# 5_spiFlash.net
KiCad netlist of a schematic drawn in Altium Designer
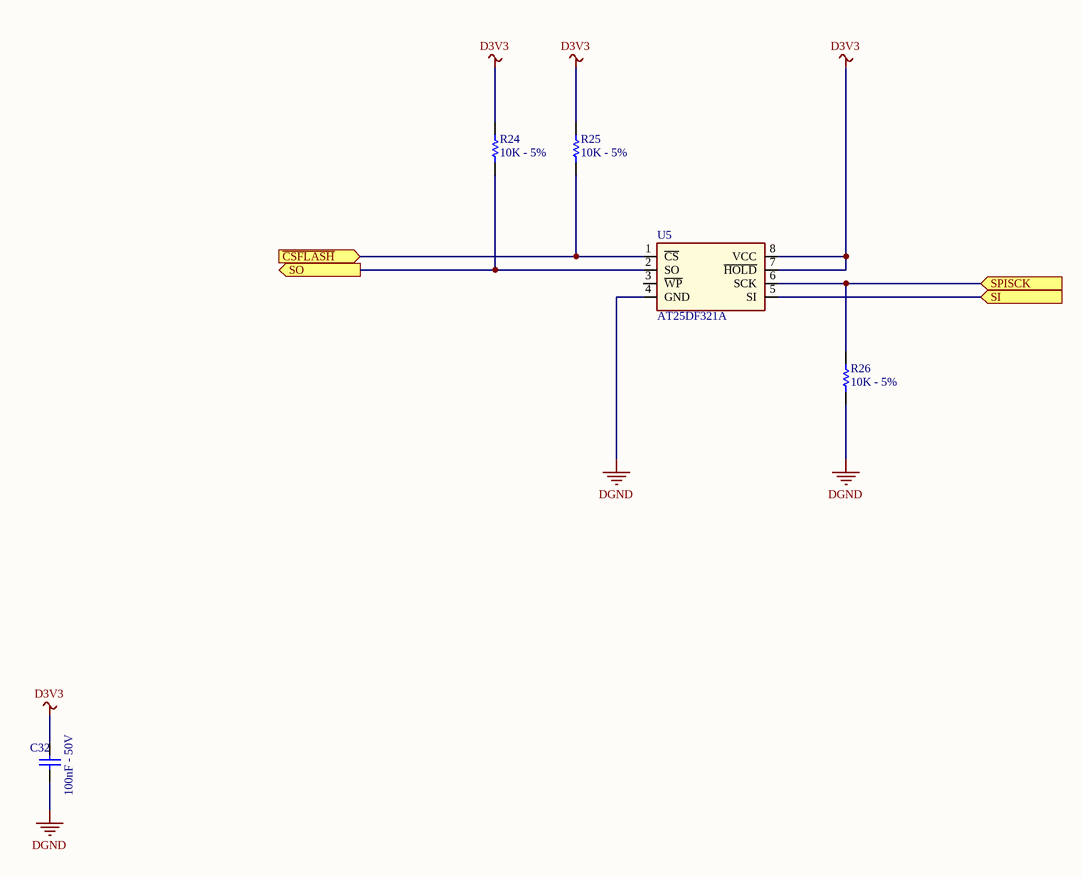
[diagram p0: 5_spiFlash.SchDoc]

(export (version "E")
  (design (tool "Eeschema 10.0.6"))
  (components
    (comp (ref "C32")
      (value "Capacitor 100 nF - 10%")
      (footprint "SMD0805-CAP")
      (description "Capacitor 100nF, 10%, SMD 0805")
      (fields
        (field (name "MANUFACTURER") "AVX")
        (field (name "PARTNUMBER") "08055C104KAT2A")
        (field (name "VALOR") "100nF - 50V")
      )
      (libsource (lib "Capacitor_smd") (part "100nF - 50V - 10% - 0805 - 580"))
    )
    (comp (ref "R24")
      (value "10K - 5% - 0805 - 328")
      (footprint "SMD0805")
      (description "Resistor 10K, 5%, SMD 0805")
      (fields
        (field (name "PARTNUMBER") "RC2012J103CS")
        (field (name "MANUFACTURER") "SAMSUNG")
        (field (name "VALOR") "10K - 5%")
      )
      (libsource (lib "Resistor_smd") (part "10K - 5% - 0805 - 328"))
    )
    (comp (ref "R25")
      (value "10K - 5% - 0805 - 328")
      (footprint "SMD0805")
      (description "Resistor 10K, 5%, SMD 0805")
      (fields
        (field (name "PARTNUMBER") "RC2012J103CS")
        (field (name "MANUFACTURER") "SAMSUNG")
        (field (name "VALOR") "10K - 5%")
      )
      (libsource (lib "Resistor_smd") (part "10K - 5% - 0805 - 328"))
    )
    (comp (ref "R26")
      (value "10K - 5% - 0805 - 328")
      (footprint "SMD0805")
      (description "Resistor 10K, 5%, SMD 0805")
      (fields
        (field (name "PARTNUMBER") "RC2012J103CS")
        (field (name "MANUFACTURER") "SAMSUNG")
        (field (name "VALOR") "10K - 5%")
      )
      (libsource (lib "Resistor_smd") (part "10K - 5% - 0805 - 328"))
    )
    (comp (ref "U5")
      (value "AT25DF321A (EIAJ SOIC) 5219")
      (footprint "BIQUAD.SOG.050/8/WG.325/L.200")
      (description "CI AT25DF321A")
      (fields
        (field (name "MANUFACTURER") "ATMEL")
        (field (name "PARTNUMBER") "AT25DF321A")
        (field (name "VALOR") "AT25DF321A")
      )
      (libsource (lib "CI_smd") (part "AT25DF321A (EIAJ SOIC) 5219"))
    )
  )
  (nets
    (net (code "1") (name "/CSFLASH") (class "Default")
      (node (ref "R25") (pin "1") (pinfunction "1_1") (pintype "passive"))
      (node (ref "U5") (pin "1") (pinfunction "~{CS}_1") (pintype "passive"))
    )
    (net (code "2") (name "/SI") (class "Default")
      (node (ref "U5") (pin "5") (pinfunction "SI_5") (pintype "passive"))
    )
    (net (code "3") (name "/SO") (class "Default")
      (node (ref "R24") (pin "1") (pinfunction "1_1") (pintype "passive"))
      (node (ref "U5") (pin "2") (pinfunction "SO_2") (pintype "passive"))
    )
    (net (code "4") (name "/SPISCK") (class "Default")
      (node (ref "R26") (pin "2") (pinfunction "2_2") (pintype "passive"))
      (node (ref "U5") (pin "6") (pinfunction "SCK_6") (pintype "passive"))
    )
    (net (code "5") (name "D3V3") (class "Default")
      (node (ref "C32") (pin "1") (pinfunction "1_1") (pintype "passive"))
      (node (ref "R24") (pin "2") (pinfunction "2_2") (pintype "passive"))
      (node (ref "R25") (pin "2") (pinfunction "2_2") (pintype "passive"))
      (node (ref "U5") (pin "7") (pinfunction "~{HOLD}_7") (pintype "passive"))
      (node (ref "U5") (pin "8") (pinfunction "VCC_8") (pintype "passive"))
    )
    (net (code "6") (name "DGND") (class "Default")
      (node (ref "C32") (pin "2") (pinfunction "2_2") (pintype "passive"))
      (node (ref "R26") (pin "1") (pinfunction "1_1") (pintype "passive"))
      (node (ref "U5") (pin "4") (pinfunction "GND_4") (pintype "passive"))
    )
    (net (code "7") (name "unconnected-(U5-~{WP}-Pad3)") (class "Default")
      (node (ref "U5") (pin "3") (pinfunction "~{WP}_3") (pintype "passive"))
    )
  )
)
